# NandFlash.net
KiCad netlist of a schematic drawn in Altium Designer
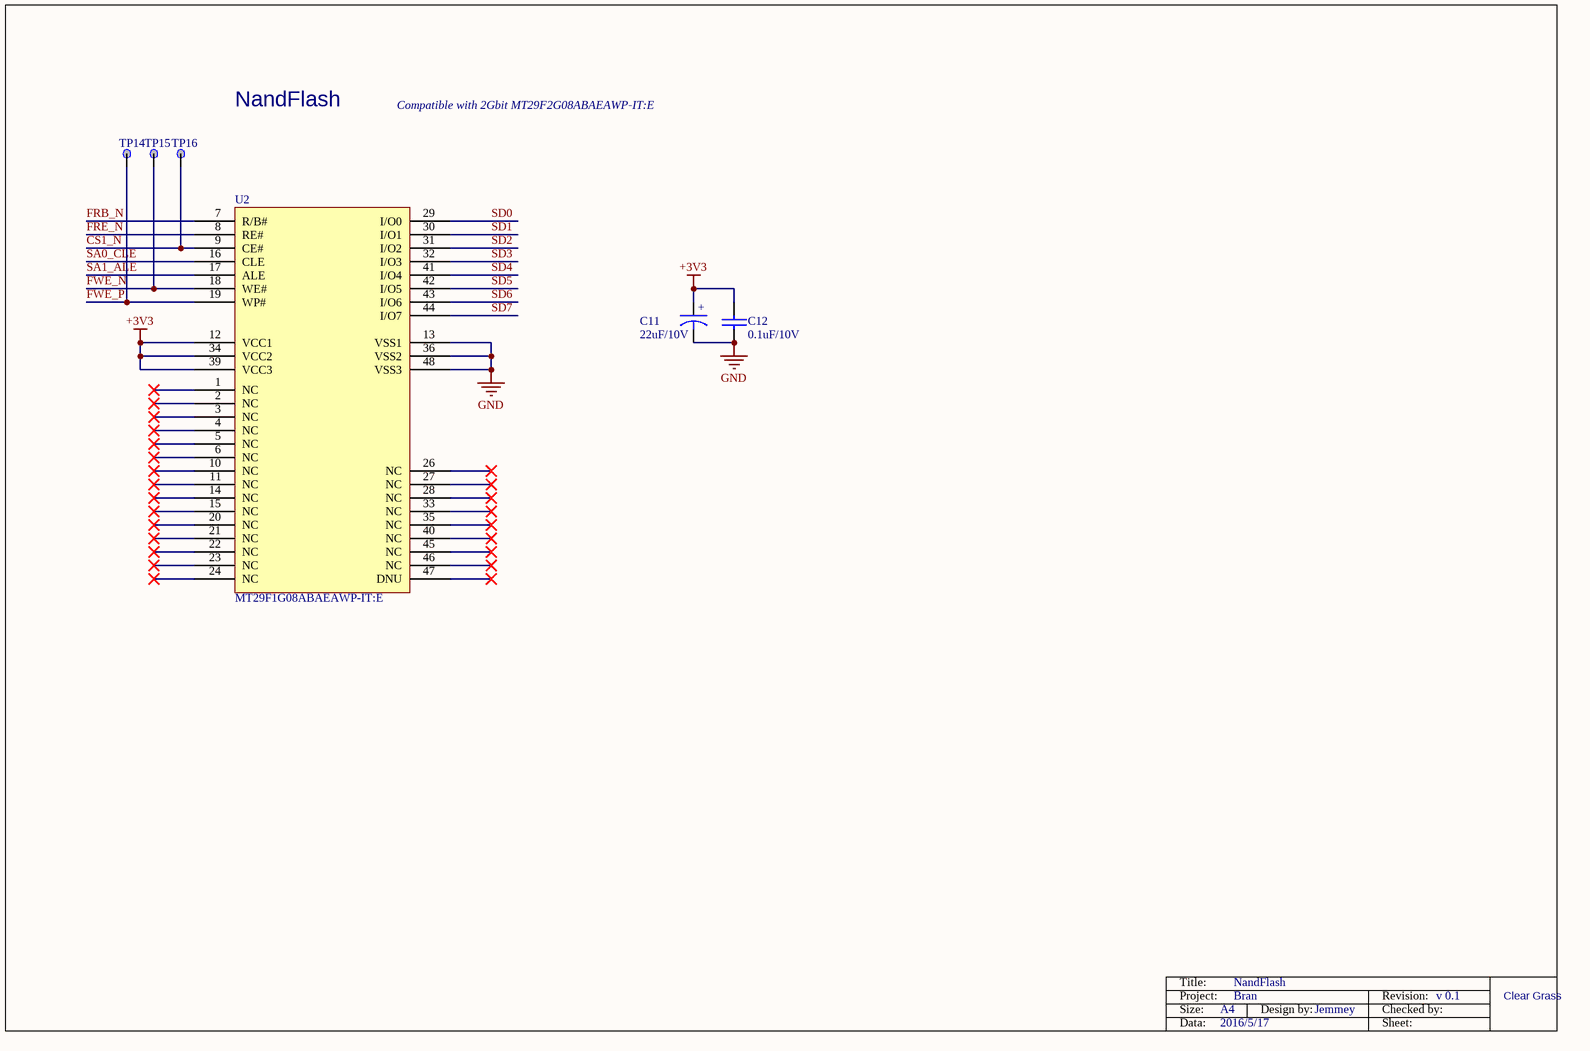
[diagram p0: NandFlash.SchDoc]

(export (version "E")
  (design (tool "Eeschema 10.0.6"))
  (components
    (comp (ref "C11") (value "22uF/10V") (footprint "6032") (libsource (lib "MoJi LIB") (part "Capacitor")))
    (comp (ref "C12")
      (value "0.1uF/10V")
      (footprint "0402C")
      (description "厂家：Murata，型号：GRM155R71A104KA01D")
      (libsource (lib "Amber") (part "CAP"))
    )
    (comp (ref "TP14") (value "TP") (footprint "TP_C40") (libsource (lib "Almos") (part "TP")))
    (comp (ref "TP15") (value "TP") (footprint "TP_C40") (libsource (lib "Almos") (part "TP")))
    (comp (ref "TP16") (value "TP") (footprint "TP_C40") (libsource (lib "Almos") (part "TP")))
    (comp (ref "U2") (value "MT29F1G08ABAEAWP-IT:E") (libsource (lib "Bran MB") (part "NandFlash")))
  )
  (nets
    (net (code "1") (name "+3V3") (class "Default")
      (node (ref "C11") (pin "1") (pinfunction "1_1") (pintype "passive"))
      (node (ref "C12") (pin "2") (pinfunction "2_2") (pintype "passive"))
      (node (ref "U2") (pin "12") (pinfunction "VCC1_12") (pintype "power_in"))
      (node (ref "U2") (pin "34") (pinfunction "VCC2_34") (pintype "power_in"))
      (node (ref "U2") (pin "39") (pinfunction "VCC3_39") (pintype "power_in"))
    )
    (net (code "2") (name "/CS1_N") (class "Default")
      (node (ref "TP16") (pin "1") (pinfunction "1_1") (pintype "passive"))
      (node (ref "U2") (pin "9") (pinfunction "CE#_9") (pintype "power_in"))
    )
    (net (code "3") (name "/FRB_N") (class "Default")
      (node (ref "U2") (pin "7") (pinfunction "R/B#_7") (pintype "power_in"))
    )
    (net (code "4") (name "/FRE_N") (class "Default")
      (node (ref "U2") (pin "8") (pinfunction "RE#_8") (pintype "power_in"))
    )
    (net (code "5") (name "/FWE_N") (class "Default")
      (node (ref "TP15") (pin "1") (pinfunction "1_1") (pintype "passive"))
      (node (ref "U2") (pin "18") (pinfunction "WE#_18") (pintype "power_in"))
    )
    (net (code "6") (name "/FWE_P") (class "Default")
      (node (ref "TP14") (pin "1") (pinfunction "1_1") (pintype "passive"))
      (node (ref "U2") (pin "19") (pinfunction "WP#_19") (pintype "power_in"))
    )
    (net (code "7") (name "/SA0_CLE") (class "Default")
      (node (ref "U2") (pin "16") (pinfunction "CLE_16") (pintype "power_in"))
    )
    (net (code "8") (name "/SA1_ALE") (class "Default")
      (node (ref "U2") (pin "17") (pinfunction "ALE_17") (pintype "power_in"))
    )
    (net (code "9") (name "/SD0") (class "Default")
      (node (ref "U2") (pin "29") (pinfunction "I/O0_29") (pintype "power_in"))
    )
    (net (code "10") (name "/SD1") (class "Default")
      (node (ref "U2") (pin "30") (pinfunction "I/O1_30") (pintype "power_in"))
    )
    (net (code "11") (name "/SD2") (class "Default")
      (node (ref "U2") (pin "31") (pinfunction "I/O2_31") (pintype "power_in"))
    )
    (net (code "12") (name "/SD3") (class "Default")
      (node (ref "U2") (pin "32") (pinfunction "I/O3_32") (pintype "power_in"))
    )
    (net (code "13") (name "/SD4") (class "Default")
      (node (ref "U2") (pin "41") (pinfunction "I/O4_41") (pintype "power_in"))
    )
    (net (code "14") (name "/SD5") (class "Default")
      (node (ref "U2") (pin "42") (pinfunction "I/O5_42") (pintype "power_in"))
    )
    (net (code "15") (name "/SD6") (class "Default")
      (node (ref "U2") (pin "43") (pinfunction "I/O6_43") (pintype "power_in"))
    )
    (net (code "16") (name "/SD7") (class "Default")
      (node (ref "U2") (pin "44") (pinfunction "I/O7_44") (pintype "power_in"))
    )
    (net (code "17") (name "GND") (class "Default")
      (node (ref "C11") (pin "2") (pinfunction "2_2") (pintype "passive"))
      (node (ref "C12") (pin "1") (pinfunction "1_1") (pintype "passive"))
      (node (ref "U2") (pin "13") (pinfunction "VSS1_13") (pintype "power_in"))
      (node (ref "U2") (pin "36") (pinfunction "VSS2_36") (pintype "power_in"))
      (node (ref "U2") (pin "48") (pinfunction "VSS3_48") (pintype "power_in"))
    )
    (net (code "18") (name "unconnected-(U2-DNU-Pad47)") (class "Default")
      (node (ref "U2") (pin "47") (pinfunction "DNU_47") (pintype "power_in+no_connect"))
    )
    (net (code "19") (name "unconnected-(U2-NC-Pad1)") (class "Default")
      (node (ref "U2") (pin "1") (pinfunction "NC_1") (pintype "power_in+no_connect"))
    )
    (net (code "20") (name "unconnected-(U2-NC-Pad2)") (class "Default")
      (node (ref "U2") (pin "2") (pinfunction "NC_2") (pintype "power_in+no_connect"))
    )
    (net (code "21") (name "unconnected-(U2-NC-Pad3)") (class "Default")
      (node (ref "U2") (pin "3") (pinfunction "NC_3") (pintype "power_in+no_connect"))
    )
    (net (code "22") (name "unconnected-(U2-NC-Pad4)") (class "Default")
      (node (ref "U2") (pin "4") (pinfunction "NC_4") (pintype "power_in+no_connect"))
    )
    (net (code "23") (name "unconnected-(U2-NC-Pad5)") (class "Default")
      (node (ref "U2") (pin "5") (pinfunction "NC_5") (pintype "power_in+no_connect"))
    )
    (net (code "24") (name "unconnected-(U2-NC-Pad6)") (class "Default")
      (node (ref "U2") (pin "6") (pinfunction "NC_6") (pintype "power_in+no_connect"))
    )
    (net (code "25") (name "unconnected-(U2-NC-Pad10)") (class "Default")
      (node (ref "U2") (pin "10") (pinfunction "NC_10") (pintype "power_in+no_connect"))
    )
    (net (code "26") (name "unconnected-(U2-NC-Pad11)") (class "Default")
      (node (ref "U2") (pin "11") (pinfunction "NC_11") (pintype "power_in+no_connect"))
    )
    (net (code "27") (name "unconnected-(U2-NC-Pad14)") (class "Default")
      (node (ref "U2") (pin "14") (pinfunction "NC_14") (pintype "power_in+no_connect"))
    )
    (net (code "28") (name "unconnected-(U2-NC-Pad15)") (class "Default")
      (node (ref "U2") (pin "15") (pinfunction "NC_15") (pintype "power_in+no_connect"))
    )
    (net (code "29") (name "unconnected-(U2-NC-Pad20)") (class "Default")
      (node (ref "U2") (pin "20") (pinfunction "NC_20") (pintype "power_in+no_connect"))
    )
    (net (code "30") (name "unconnected-(U2-NC-Pad21)") (class "Default")
      (node (ref "U2") (pin "21") (pinfunction "NC_21") (pintype "power_in+no_connect"))
    )
    (net (code "31") (name "unconnected-(U2-NC-Pad22)") (class "Default")
      (node (ref "U2") (pin "22") (pinfunction "NC_22") (pintype "power_in+no_connect"))
    )
    (net (code "32") (name "unconnected-(U2-NC-Pad23)") (class "Default")
      (node (ref "U2") (pin "23") (pinfunction "NC_23") (pintype "power_in+no_connect"))
    )
    (net (code "33") (name "unconnected-(U2-NC-Pad24)") (class "Default")
      (node (ref "U2") (pin "24") (pinfunction "NC_24") (pintype "power_in+no_connect"))
    )
    (net (code "34") (name "unconnected-(U2-NC-Pad26)") (class "Default")
      (node (ref "U2") (pin "26") (pinfunction "NC_26") (pintype "power_in+no_connect"))
    )
    (net (code "35") (name "unconnected-(U2-NC-Pad27)") (class "Default")
      (node (ref "U2") (pin "27") (pinfunction "NC_27") (pintype "power_in+no_connect"))
    )
    (net (code "36") (name "unconnected-(U2-NC-Pad28)") (class "Default")
      (node (ref "U2") (pin "28") (pinfunction "NC_28") (pintype "power_in+no_connect"))
    )
    (net (code "37") (name "unconnected-(U2-NC-Pad33)") (class "Default")
      (node (ref "U2") (pin "33") (pinfunction "NC_33") (pintype "power_in+no_connect"))
    )
    (net (code "38") (name "unconnected-(U2-NC-Pad35)") (class "Default")
      (node (ref "U2") (pin "35") (pinfunction "NC_35") (pintype "power_in+no_connect"))
    )
    (net (code "39") (name "unconnected-(U2-NC-Pad40)") (class "Default")
      (node (ref "U2") (pin "40") (pinfunction "NC_40") (pintype "power_in+no_connect"))
    )
    (net (code "40") (name "unconnected-(U2-NC-Pad45)") (class "Default")
      (node (ref "U2") (pin "45") (pinfunction "NC_45") (pintype "power_in+no_connect"))
    )
    (net (code "41") (name "unconnected-(U2-NC-Pad46)") (class "Default")
      (node (ref "U2") (pin "46") (pinfunction "NC_46") (pintype "power_in+no_connect"))
    )
  )
)
